# keypad.net
KiCad netlist of a schematic drawn in EAGLE
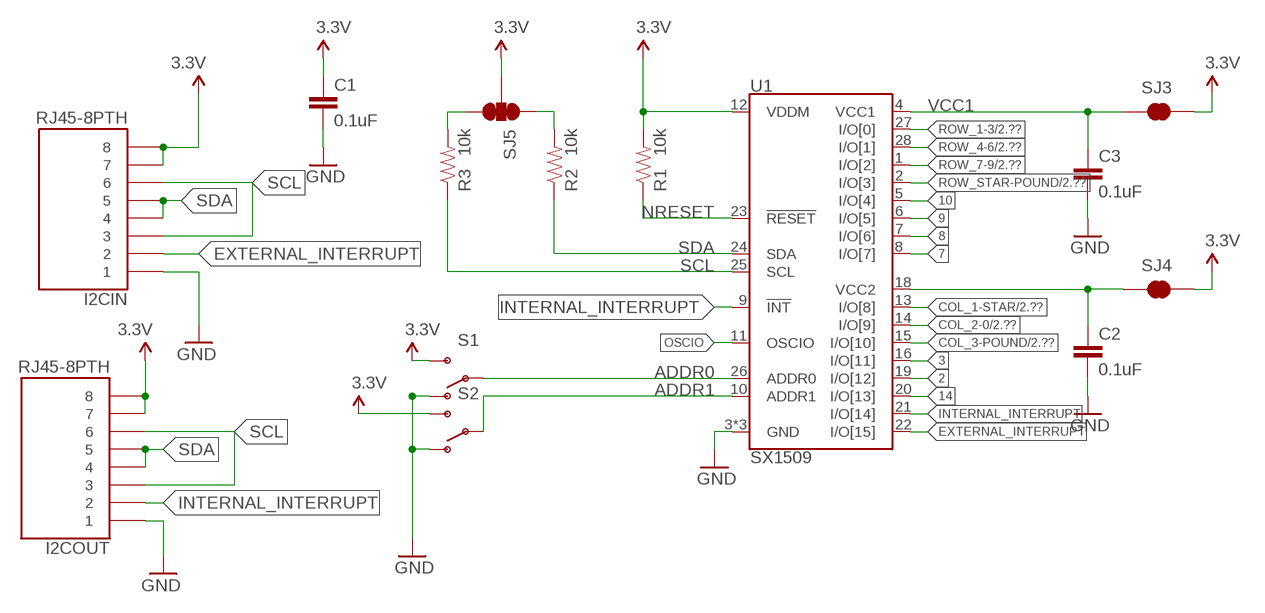
[diagram p0: schematic, sheet 1]
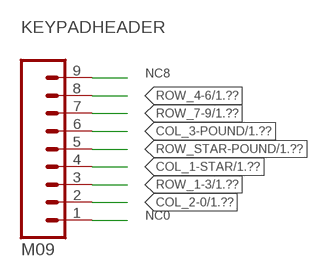
[diagram p1: schematic, sheet 2]

(export (version "E")
  (design (tool "Eeschema 10.0.6"))
  (components
    (comp (ref "KEYPADHEADER")
      (value "M09")
      (footprint "eagle-import:1X09")
      (libsource (lib "eagle-import") (part "M09"))
    )
    (comp (ref "C1")
      (value "0.1uF")
      (footprint "eagle-import:0402-CAP")
      (libsource (lib "eagle-import") (part "CAP0402-CAP"))
    )
    (comp (ref "C2")
      (value "0.1uF")
      (footprint "eagle-import:0402-CAP")
      (libsource (lib "eagle-import") (part "CAP0402-CAP"))
    )
    (comp (ref "C3")
      (value "0.1uF")
      (footprint "eagle-import:0402-CAP")
      (libsource (lib "eagle-import") (part "CAP0402-CAP"))
    )
    (comp (ref "I2CIN")
      (value "RJ45-8PTH")
      (footprint "eagle-import:RJ45-8")
      (libsource (lib "eagle-import") (part "RJ45-8PTH"))
    )
    (comp (ref "I2COUT")
      (value "RJ45-8PTH")
      (footprint "eagle-import:RJ45-8")
      (libsource (lib "eagle-import") (part "RJ45-8PTH"))
    )
    (comp (ref "R1")
      (value "10k")
      (footprint "eagle-import:0402-RES")
      (libsource (lib "eagle-import") (part "RESISTOR0402-RES"))
    )
    (comp (ref "R2")
      (value "10k")
      (footprint "eagle-import:0402-RES")
      (libsource (lib "eagle-import") (part "RESISTOR0402-RES"))
    )
    (comp (ref "R3")
      (value "10k")
      (footprint "eagle-import:0402-RES")
      (libsource (lib "eagle-import") (part "RESISTOR0402-RES"))
    )
    (comp (ref "S1")
      (value "SWITCH-SPDT-SMD-A")
      (footprint "eagle-import:SWITCH-SPST-SMD-A")
      (libsource (lib "eagle-import") (part "SWITCH-SPDT-SMD-A"))
    )
    (comp (ref "S2")
      (value "SWITCH-SPDT-SMD-A")
      (footprint "eagle-import:SWITCH-SPST-SMD-A")
      (libsource (lib "eagle-import") (part "SWITCH-SPDT-SMD-A"))
    )
    (comp (ref "SJ3")
      (value "SOLDERJUMPERNO")
      (footprint "eagle-import:SJ_2S-NO")
      (libsource (lib "eagle-import") (part "SOLDERJUMPERNO"))
    )
    (comp (ref "SJ4")
      (value "SOLDERJUMPERNO")
      (footprint "eagle-import:SJ_2S-NO")
      (libsource (lib "eagle-import") (part "SOLDERJUMPERNO"))
    )
    (comp (ref "SJ5")
      (value "SOLDERJUMPER_2WAYS")
      (footprint "eagle-import:SJ_3")
      (libsource (lib "eagle-import") (part "SOLDERJUMPER_2WAYS"))
    )
    (comp (ref "U1")
      (value "SX1509")
      (footprint "eagle-import:QFN-28")
      (libsource (lib "eagle-import") (part "SX1509"))
    )
  )
  (nets
    (net (code "1") (name "2") (class "Default")
      (node (ref "U1") (pin "19") (pinfunction "I/O[12]_19") (pintype "bidirectional"))
    )
    (net (code "2") (name "3") (class "Default")
      (node (ref "U1") (pin "16") (pinfunction "I/O[11]_16") (pintype "bidirectional"))
    )
    (net (code "3") (name "3.3V") (class "Default")
      (node (ref "C1") (pin "1") (pinfunction "1_1") (pintype "passive"))
      (node (ref "I2CIN") (pin "7") (pinfunction "7_7") (pintype "bidirectional"))
      (node (ref "I2CIN") (pin "8") (pinfunction "8_8") (pintype "bidirectional"))
      (node (ref "I2COUT") (pin "7") (pinfunction "7_7") (pintype "bidirectional"))
      (node (ref "I2COUT") (pin "8") (pinfunction "8_8") (pintype "bidirectional"))
      (node (ref "R1") (pin "2") (pinfunction "2_2") (pintype "passive"))
      (node (ref "S1") (pin "3") (pinfunction "S_3") (pintype "passive"))
      (node (ref "S2") (pin "3") (pinfunction "S_3") (pintype "passive"))
      (node (ref "SJ3") (pin "2") (pinfunction "2_2") (pintype "passive"))
      (node (ref "SJ4") (pin "2") (pinfunction "2_2") (pintype "passive"))
      (node (ref "SJ5") (pin "2") (pinfunction "2_2") (pintype "passive"))
      (node (ref "U1") (pin "12") (pinfunction "VDDM_12") (pintype "bidirectional"))
    )
    (net (code "4") (name "7") (class "Default")
      (node (ref "U1") (pin "8") (pinfunction "I/O[7]_8") (pintype "bidirectional"))
    )
    (net (code "5") (name "8") (class "Default")
      (node (ref "U1") (pin "7") (pinfunction "I/O[6]_7") (pintype "bidirectional"))
    )
    (net (code "6") (name "9") (class "Default")
      (node (ref "U1") (pin "6") (pinfunction "I/O[5]_6") (pintype "bidirectional"))
    )
    (net (code "7") (name "10") (class "Default")
      (node (ref "U1") (pin "5") (pinfunction "I/O[4]_5") (pintype "bidirectional"))
    )
    (net (code "8") (name "14") (class "Default")
      (node (ref "U1") (pin "20") (pinfunction "I/O[13]_20") (pintype "bidirectional"))
    )
    (net (code "9") (name "ADDR0") (class "Default")
      (node (ref "S1") (pin "2") (pinfunction "P_2") (pintype "passive"))
      (node (ref "U1") (pin "26") (pinfunction "ADDR0_26") (pintype "bidirectional"))
    )
    (net (code "10") (name "ADDR1") (class "Default")
      (node (ref "S2") (pin "2") (pinfunction "P_2") (pintype "passive"))
      (node (ref "U1") (pin "10") (pinfunction "ADDR1_10") (pintype "bidirectional"))
    )
    (net (code "11") (name "COL_1-STAR") (class "Default")
      (node (ref "KEYPADHEADER") (pin "4") (pinfunction "4_4") (pintype "passive"))
      (node (ref "U1") (pin "13") (pinfunction "I/O[8]_13") (pintype "bidirectional"))
    )
    (net (code "12") (name "COL_2-0") (class "Default")
      (node (ref "KEYPADHEADER") (pin "2") (pinfunction "2_2") (pintype "passive"))
      (node (ref "U1") (pin "14") (pinfunction "I/O[9]_14") (pintype "bidirectional"))
    )
    (net (code "13") (name "COL_3-POUND") (class "Default")
      (node (ref "KEYPADHEADER") (pin "6") (pinfunction "6_6") (pintype "passive"))
      (node (ref "U1") (pin "15") (pinfunction "I/O[10]_15") (pintype "bidirectional"))
    )
    (net (code "14") (name "EXTERNAL_INTERRUPT") (class "Default")
      (node (ref "I2CIN") (pin "2") (pinfunction "2_2") (pintype "bidirectional"))
      (node (ref "U1") (pin "22") (pinfunction "I/O[15]_22") (pintype "bidirectional"))
    )
    (net (code "15") (name "GND") (class "Default")
      (node (ref "C1") (pin "2") (pinfunction "2_2") (pintype "passive"))
      (node (ref "C2") (pin "2") (pinfunction "2_2") (pintype "passive"))
      (node (ref "C3") (pin "2") (pinfunction "2_2") (pintype "passive"))
      (node (ref "I2CIN") (pin "1") (pinfunction "1_1") (pintype "bidirectional"))
      (node (ref "I2COUT") (pin "1") (pinfunction "1_1") (pintype "bidirectional"))
      (node (ref "S1") (pin "1") (pinfunction "O_1") (pintype "passive"))
      (node (ref "S2") (pin "1") (pinfunction "O_1") (pintype "passive"))
      (node (ref "U1") (pin "17") (pinfunction "GND_17") (pintype "bidirectional"))
      (node (ref "U1") (pin "29") (pinfunction "GND_29") (pintype "bidirectional"))
      (node (ref "U1") (pin "3") (pinfunction "GND_3") (pintype "bidirectional"))
    )
    (net (code "16") (name "INTERNAL_INTERRUPT") (class "Default")
      (node (ref "I2COUT") (pin "2") (pinfunction "2_2") (pintype "bidirectional"))
      (node (ref "U1") (pin "21") (pinfunction "I/O[14]_21") (pintype "bidirectional"))
      (node (ref "U1") (pin "9") (pinfunction "~{INT}_9") (pintype "bidirectional"))
    )
    (net (code "17") (name "NC0") (class "Default")
      (node (ref "KEYPADHEADER") (pin "1") (pinfunction "1_1") (pintype "passive"))
    )
    (net (code "18") (name "NC8") (class "Default")
      (node (ref "KEYPADHEADER") (pin "9") (pinfunction "9_9") (pintype "passive"))
    )
    (net (code "19") (name "NRESET") (class "Default")
      (node (ref "R1") (pin "1") (pinfunction "1_1") (pintype "passive"))
      (node (ref "U1") (pin "23") (pinfunction "~{RESET}_23") (pintype "bidirectional"))
    )
    (net (code "20") (name "Net-(R2-Pad2)") (class "Default")
      (node (ref "R2") (pin "2") (pinfunction "2_2") (pintype "passive"))
      (node (ref "SJ5") (pin "1") (pinfunction "1_1") (pintype "passive"))
    )
    (net (code "21") (name "Net-(R3-Pad2)") (class "Default")
      (node (ref "R3") (pin "2") (pinfunction "2_2") (pintype "passive"))
      (node (ref "SJ5") (pin "3") (pinfunction "3_3") (pintype "passive"))
    )
    (net (code "22") (name "Net-(U1-VCC2)") (class "Default")
      (node (ref "C2") (pin "1") (pinfunction "1_1") (pintype "passive"))
      (node (ref "SJ4") (pin "1") (pinfunction "1_1") (pintype "passive"))
      (node (ref "U1") (pin "18") (pinfunction "VCC2_18") (pintype "bidirectional"))
    )
    (net (code "23") (name "OSCIO") (class "Default")
      (node (ref "U1") (pin "11") (pinfunction "OSCIO_11") (pintype "bidirectional"))
    )
    (net (code "24") (name "ROW_1-3") (class "Default")
      (node (ref "KEYPADHEADER") (pin "3") (pinfunction "3_3") (pintype "passive"))
      (node (ref "U1") (pin "27") (pinfunction "I/O[0]_27") (pintype "bidirectional"))
    )
    (net (code "25") (name "ROW_4-6") (class "Default")
      (node (ref "KEYPADHEADER") (pin "8") (pinfunction "8_8") (pintype "passive"))
      (node (ref "U1") (pin "28") (pinfunction "I/O[1]_28") (pintype "bidirectional"))
    )
    (net (code "26") (name "ROW_7-9") (class "Default")
      (node (ref "KEYPADHEADER") (pin "7") (pinfunction "7_7") (pintype "passive"))
      (node (ref "U1") (pin "1") (pinfunction "I/O[2]_1") (pintype "bidirectional"))
    )
    (net (code "27") (name "ROW_STAR-POUND") (class "Default")
      (node (ref "KEYPADHEADER") (pin "5") (pinfunction "5_5") (pintype "passive"))
      (node (ref "U1") (pin "2") (pinfunction "I/O[3]_2") (pintype "bidirectional"))
    )
    (net (code "28") (name "SCL") (class "Default")
      (node (ref "I2CIN") (pin "3") (pinfunction "3_3") (pintype "bidirectional"))
      (node (ref "I2CIN") (pin "6") (pinfunction "6_6") (pintype "bidirectional"))
      (node (ref "I2COUT") (pin "3") (pinfunction "3_3") (pintype "bidirectional"))
      (node (ref "I2COUT") (pin "6") (pinfunction "6_6") (pintype "bidirectional"))
      (node (ref "R3") (pin "1") (pinfunction "1_1") (pintype "passive"))
      (node (ref "U1") (pin "25") (pinfunction "SCL_25") (pintype "bidirectional"))
    )
    (net (code "29") (name "SDA") (class "Default")
      (node (ref "I2CIN") (pin "4") (pinfunction "4_4") (pintype "bidirectional"))
      (node (ref "I2CIN") (pin "5") (pinfunction "5_5") (pintype "bidirectional"))
      (node (ref "I2COUT") (pin "4") (pinfunction "4_4") (pintype "bidirectional"))
      (node (ref "I2COUT") (pin "5") (pinfunction "5_5") (pintype "bidirectional"))
      (node (ref "R2") (pin "1") (pinfunction "1_1") (pintype "passive"))
      (node (ref "U1") (pin "24") (pinfunction "SDA_24") (pintype "bidirectional"))
    )
    (net (code "30") (name "VCC1") (class "Default")
      (node (ref "C3") (pin "1") (pinfunction "1_1") (pintype "passive"))
      (node (ref "SJ3") (pin "1") (pinfunction "1_1") (pintype "passive"))
      (node (ref "U1") (pin "4") (pinfunction "VCC1_4") (pintype "bidirectional"))
    )
  )
)
